# FPGA3.net
KiCad netlist of a schematic drawn in Altium Designer
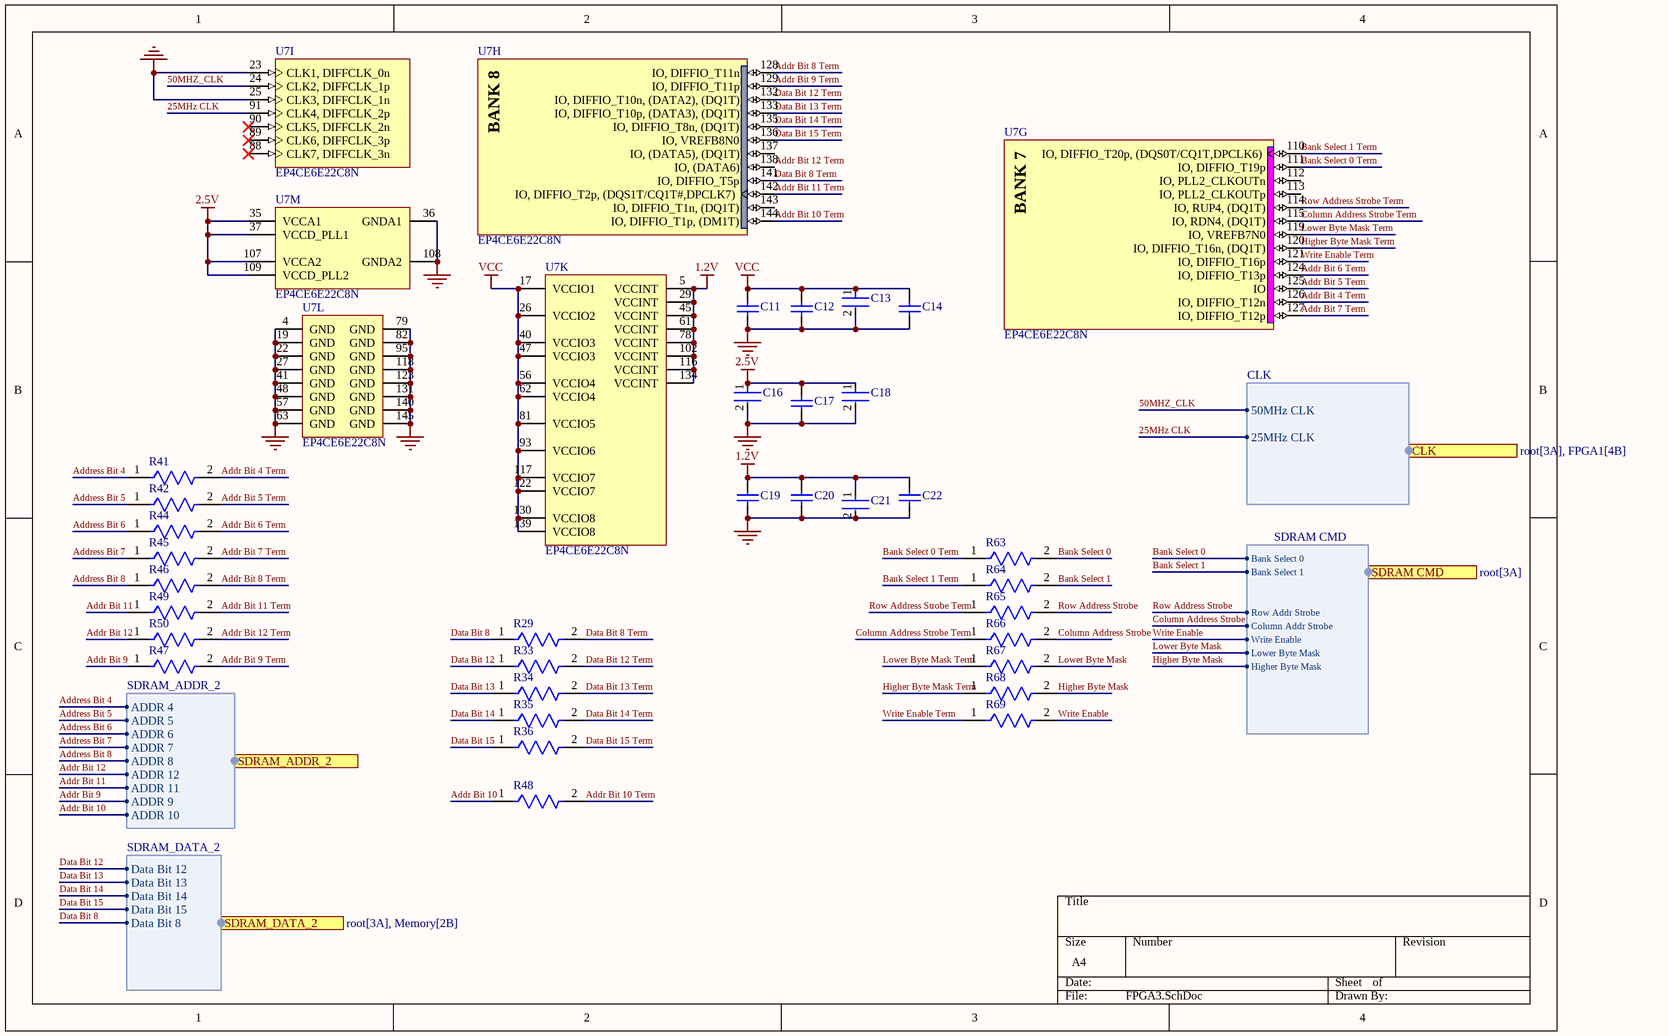
[diagram p0: FPGA3.SchDoc]

(export (version "E")
  (design (tool "Eeschema 10.0.6"))
  (components
    (comp (ref "C11")
      (value "C0603C105K9PACTU")
      (footprint "CAPC1608X90X35LL15T15")
      (fields (field (name "MANUFACTURER") "Kemet"))
      (libsource (lib "Altium Content Vault") (part "CAP"))
    )
    (comp (ref "C12")
      (value "C0603C105K9PACTU")
      (footprint "CAPC1608X90X35LL15T15")
      (fields (field (name "MANUFACTURER") "Kemet"))
      (libsource (lib "Altium Content Vault") (part "CAP"))
    )
    (comp (ref "C13")
      (value "CC0603KRX7R9BB104")
      (footprint "FP-CC0603-DA-MFG")
      (description "CAP CER 0.1UF 50V X7R 0603")
      (fields (field (name "MANUFACTURER") "YAGEO") (field (name "VOLTAGE") "50 V"))
      (libsource (lib "Altium Content Vault") (part "11868f565c42a9108669ba33697ecf6"))
    )
    (comp (ref "C14")
      (value "C0805S472K5RACTU")
      (footprint "CAPC2013X145X50ML20T25")
      (fields (field (name "MANUFACTURER") "Kemet"))
      (libsource (lib "Altium Content Vault") (part "CAP"))
    )
    (comp (ref "C16")
      (value "CL10B102KB8NNNC")
      (footprint "FP-CL10-IPC_C")
      (description "Cap Ceramic 1nF 50V X7R ±10% Pad SMD 0603 +125°C T/R")
      (fields (field (name "VOLTAGE") "50V") (field (name "TOLERANCE") "10%"))
      (libsource (lib "Altium Content Vault") (part "b4654b650e69147ec39a6b967a45e02"))
    )
    (comp (ref "C17")
      (value "C0805S472K5RACTU")
      (footprint "CAPC2013X145X50ML20T25")
      (fields (field (name "MANUFACTURER") "Kemet"))
      (libsource (lib "Altium Content Vault") (part "CAP"))
    )
    (comp (ref "C18")
      (value "CC0603KRX7R9BB104")
      (footprint "FP-CC0603-DA-MFG")
      (description "CAP CER 0.1UF 50V X7R 0603")
      (fields (field (name "MANUFACTURER") "YAGEO") (field (name "VOLTAGE") "50 V"))
      (libsource (lib "Altium Content Vault") (part "11868f565c42a9108669ba33697ecf6"))
    )
    (comp (ref "C19")
      (value "C0603C105K9PACTU")
      (footprint "CAPC1608X90X35LL15T15")
      (fields (field (name "MANUFACTURER") "Kemet"))
      (libsource (lib "Altium Content Vault") (part "CAP"))
    )
    (comp (ref "C20")
      (value "C0603C105K9PACTU")
      (footprint "CAPC1608X90X35LL15T15")
      (fields (field (name "MANUFACTURER") "Kemet"))
      (libsource (lib "Altium Content Vault") (part "CAP"))
    )
    (comp (ref "C21")
      (value "CC0603KRX7R9BB104")
      (footprint "FP-CC0603-DA-MFG")
      (description "CAP CER 0.1UF 50V X7R 0603")
      (fields (field (name "MANUFACTURER") "YAGEO") (field (name "VOLTAGE") "50 V"))
      (libsource (lib "Altium Content Vault") (part "11868f565c42a9108669ba33697ecf6"))
    )
    (comp (ref "C22")
      (value "C0805S472K5RACTU")
      (footprint "CAPC2013X145X50ML20T25")
      (fields (field (name "MANUFACTURER") "Kemet"))
      (libsource (lib "Altium Content Vault") (part "CAP"))
    )
    (comp (ref "R29")
      (value "RT0402BRE0750RL")
      (footprint "FP-RT0402-0_35-MFG")
      (fields (field (name "TOLERANCE") "0.1%"))
      (libsource (lib "Altium Content Vault") (part "1029c3af85768c4190bb7ad29bc67b5"))
    )
    (comp (ref "R33")
      (value "RT0402BRE0750RL")
      (footprint "FP-RT0402-0_35-MFG")
      (fields (field (name "TOLERANCE") "0.1%"))
      (libsource (lib "Altium Content Vault") (part "1029c3af85768c4190bb7ad29bc67b5"))
    )
    (comp (ref "R34")
      (value "RT0402BRE0750RL")
      (footprint "FP-RT0402-0_35-MFG")
      (fields (field (name "TOLERANCE") "0.1%"))
      (libsource (lib "Altium Content Vault") (part "1029c3af85768c4190bb7ad29bc67b5"))
    )
    (comp (ref "R35")
      (value "RT0402BRE0750RL")
      (footprint "FP-RT0402-0_35-MFG")
      (fields (field (name "TOLERANCE") "0.1%"))
      (libsource (lib "Altium Content Vault") (part "1029c3af85768c4190bb7ad29bc67b5"))
    )
    (comp (ref "R36")
      (value "RT0402BRE0750RL")
      (footprint "FP-RT0402-0_35-MFG")
      (fields (field (name "TOLERANCE") "0.1%"))
      (libsource (lib "Altium Content Vault") (part "1029c3af85768c4190bb7ad29bc67b5"))
    )
    (comp (ref "R41")
      (value "RT0402BRE0750RL")
      (footprint "FP-RT0402-0_35-MFG")
      (fields (field (name "TOLERANCE") "0.1%"))
      (libsource (lib "Altium Content Vault") (part "1029c3af85768c4190bb7ad29bc67b5"))
    )
    (comp (ref "R42")
      (value "RT0402BRE0750RL")
      (footprint "FP-RT0402-0_35-MFG")
      (fields (field (name "TOLERANCE") "0.1%"))
      (libsource (lib "Altium Content Vault") (part "1029c3af85768c4190bb7ad29bc67b5"))
    )
    (comp (ref "R44")
      (value "RT0402BRE0750RL")
      (footprint "FP-RT0402-0_35-MFG")
      (fields (field (name "TOLERANCE") "0.1%"))
      (libsource (lib "Altium Content Vault") (part "1029c3af85768c4190bb7ad29bc67b5"))
    )
    (comp (ref "R45")
      (value "RT0402BRE0750RL")
      (footprint "FP-RT0402-0_35-MFG")
      (fields (field (name "TOLERANCE") "0.1%"))
      (libsource (lib "Altium Content Vault") (part "1029c3af85768c4190bb7ad29bc67b5"))
    )
    (comp (ref "R46")
      (value "RT0402BRE0750RL")
      (footprint "FP-RT0402-0_35-MFG")
      (fields (field (name "TOLERANCE") "0.1%"))
      (libsource (lib "Altium Content Vault") (part "1029c3af85768c4190bb7ad29bc67b5"))
    )
    (comp (ref "R47")
      (value "RT0402BRE0750RL")
      (footprint "FP-RT0402-0_35-MFG")
      (fields (field (name "TOLERANCE") "0.1%"))
      (libsource (lib "Altium Content Vault") (part "1029c3af85768c4190bb7ad29bc67b5"))
    )
    (comp (ref "R48")
      (value "RT0402BRE0750RL")
      (footprint "FP-RT0402-0_35-MFG")
      (fields (field (name "TOLERANCE") "0.1%"))
      (libsource (lib "Altium Content Vault") (part "1029c3af85768c4190bb7ad29bc67b5"))
    )
    (comp (ref "R49")
      (value "RT0402BRE0750RL")
      (footprint "FP-RT0402-0_35-MFG")
      (fields (field (name "TOLERANCE") "0.1%"))
      (libsource (lib "Altium Content Vault") (part "1029c3af85768c4190bb7ad29bc67b5"))
    )
    (comp (ref "R50")
      (value "RT0402BRE0750RL")
      (footprint "FP-RT0402-0_35-MFG")
      (fields (field (name "TOLERANCE") "0.1%"))
      (libsource (lib "Altium Content Vault") (part "1029c3af85768c4190bb7ad29bc67b5"))
    )
    (comp (ref "R63")
      (value "RT0402BRE0750RL")
      (footprint "FP-RT0402-0_35-MFG")
      (fields (field (name "TOLERANCE") "0.1%"))
      (libsource (lib "Altium Content Vault") (part "1029c3af85768c4190bb7ad29bc67b5"))
    )
    (comp (ref "R64")
      (value "RT0402BRE0750RL")
      (footprint "FP-RT0402-0_35-MFG")
      (fields (field (name "TOLERANCE") "0.1%"))
      (libsource (lib "Altium Content Vault") (part "1029c3af85768c4190bb7ad29bc67b5"))
    )
    (comp (ref "R65")
      (value "RT0402BRE0750RL")
      (footprint "FP-RT0402-0_35-MFG")
      (fields (field (name "TOLERANCE") "0.1%"))
      (libsource (lib "Altium Content Vault") (part "1029c3af85768c4190bb7ad29bc67b5"))
    )
    (comp (ref "R66")
      (value "RT0402BRE0750RL")
      (footprint "FP-RT0402-0_35-MFG")
      (fields (field (name "TOLERANCE") "0.1%"))
      (libsource (lib "Altium Content Vault") (part "1029c3af85768c4190bb7ad29bc67b5"))
    )
    (comp (ref "R67")
      (value "RT0402BRE0750RL")
      (footprint "FP-RT0402-0_35-MFG")
      (fields (field (name "TOLERANCE") "0.1%"))
      (libsource (lib "Altium Content Vault") (part "1029c3af85768c4190bb7ad29bc67b5"))
    )
    (comp (ref "R68")
      (value "RT0402BRE0750RL")
      (footprint "FP-RT0402-0_35-MFG")
      (fields (field (name "TOLERANCE") "0.1%"))
      (libsource (lib "Altium Content Vault") (part "1029c3af85768c4190bb7ad29bc67b5"))
    )
    (comp (ref "R69")
      (value "RT0402BRE0750RL")
      (footprint "FP-RT0402-0_35-MFG")
      (fields (field (name "TOLERANCE") "0.1%"))
      (libsource (lib "Altium Content Vault") (part "1029c3af85768c4190bb7ad29bc67b5"))
    )
    (comp (ref "U7")
      (value "EP4CE6E22C8N")
      (footprint "EQFP144_A-165_D2-54_M")
      (fields (field (name "MANUFACTURER") "Altera"))
      (libsource (lib "Altium Content Vault") (part "FPGA-ALEP4C-EP4CE6-E144"))
    )
  )
  (nets
    (net (code "6") (name "/25MHz CLK") (class "Default")
      (node (ref "U7") (pin "91") (pinfunction "CLK4,_DIFFCLK_2p_91") (pintype "input"))
    )
    (net (code "7") (name "/50MHZ_CLK") (class "Default")
      (node (ref "U7") (pin "24") (pinfunction "CLK2,_DIFFCLK_1p_24") (pintype "input"))
    )
    (net (code "8") (name "/Addr Bit 4 Term") (class "Default")
      (node (ref "R41") (pin "2") (pinfunction "2_2") (pintype "passive"))
      (node (ref "U7") (pin "126") (pinfunction "IO,_DIFFIO_T12n_126") (pintype "bidirectional"))
    )
    (net (code "9") (name "/Addr Bit 5 Term") (class "Default")
      (node (ref "R42") (pin "2") (pinfunction "2_2") (pintype "passive"))
      (node (ref "U7") (pin "125") (pinfunction "IO_125") (pintype "bidirectional"))
    )
    (net (code "10") (name "/Addr Bit 6 Term") (class "Default")
      (node (ref "R44") (pin "2") (pinfunction "2_2") (pintype "passive"))
      (node (ref "U7") (pin "124") (pinfunction "IO,_DIFFIO_T13p_124") (pintype "bidirectional"))
    )
    (net (code "11") (name "/Addr Bit 7 Term") (class "Default")
      (node (ref "R45") (pin "2") (pinfunction "2_2") (pintype "passive"))
      (node (ref "U7") (pin "127") (pinfunction "IO,_DIFFIO_T12p_127") (pintype "bidirectional"))
    )
    (net (code "12") (name "/Addr Bit 8 Term") (class "Default")
      (node (ref "R46") (pin "2") (pinfunction "2_2") (pintype "passive"))
      (node (ref "U7") (pin "128") (pinfunction "IO,_DIFFIO_T11n_128") (pintype "bidirectional"))
    )
    (net (code "13") (name "/Addr Bit 9") (class "Default")
      (node (ref "R47") (pin "1") (pinfunction "1_1") (pintype "passive"))
    )
    (net (code "14") (name "/Addr Bit 9 Term") (class "Default")
      (node (ref "R47") (pin "2") (pinfunction "2_2") (pintype "passive"))
      (node (ref "U7") (pin "129") (pinfunction "IO,_DIFFIO_T11p_129") (pintype "bidirectional"))
    )
    (net (code "15") (name "/Addr Bit 10") (class "Default")
      (node (ref "R48") (pin "1") (pinfunction "1_1") (pintype "passive"))
    )
    (net (code "16") (name "/Addr Bit 10 Term") (class "Default")
      (node (ref "R48") (pin "2") (pinfunction "2_2") (pintype "passive"))
      (node (ref "U7") (pin "144") (pinfunction "IO,_DIFFIO_T1p,_(DM1T)_144") (pintype "bidirectional"))
    )
    (net (code "17") (name "/Addr Bit 11") (class "Default")
      (node (ref "R49") (pin "1") (pinfunction "1_1") (pintype "passive"))
    )
    (net (code "18") (name "/Addr Bit 11 Term") (class "Default")
      (node (ref "R49") (pin "2") (pinfunction "2_2") (pintype "passive"))
      (node (ref "U7") (pin "142") (pinfunction "IO,_DIFFIO_T2p,_(DQS1T/CQ1T#,DPCLK7)_142") (pintype "bidirectional"))
    )
    (net (code "19") (name "/Addr Bit 12") (class "Default")
      (node (ref "R50") (pin "1") (pinfunction "1_1") (pintype "passive"))
    )
    (net (code "20") (name "/Addr Bit 12 Term") (class "Default")
      (node (ref "R50") (pin "2") (pinfunction "2_2") (pintype "passive"))
      (node (ref "U7") (pin "138") (pinfunction "IO,_(DATA6)_138") (pintype "bidirectional"))
    )
    (net (code "21") (name "/Address Bit 4") (class "Default")
      (node (ref "R41") (pin "1") (pinfunction "1_1") (pintype "passive"))
    )
    (net (code "22") (name "/Address Bit 5") (class "Default")
      (node (ref "R42") (pin "1") (pinfunction "1_1") (pintype "passive"))
    )
    (net (code "23") (name "/Address Bit 6") (class "Default")
      (node (ref "R44") (pin "1") (pinfunction "1_1") (pintype "passive"))
    )
    (net (code "24") (name "/Address Bit 7") (class "Default")
      (node (ref "R45") (pin "1") (pinfunction "1_1") (pintype "passive"))
    )
    (net (code "25") (name "/Address Bit 8") (class "Default")
      (node (ref "R46") (pin "1") (pinfunction "1_1") (pintype "passive"))
    )
    (net (code "26") (name "/Bank Select 0") (class "Default")
      (node (ref "R63") (pin "2") (pinfunction "2_2") (pintype "passive"))
    )
    (net (code "27") (name "/Bank Select 0 Term") (class "Default")
      (node (ref "R63") (pin "1") (pinfunction "1_1") (pintype "passive"))
      (node (ref "U7") (pin "111") (pinfunction "IO,_DIFFIO_T19p_111") (pintype "bidirectional"))
    )
    (net (code "28") (name "/Bank Select 1") (class "Default")
      (node (ref "R64") (pin "2") (pinfunction "2_2") (pintype "passive"))
    )
    (net (code "29") (name "/Bank Select 1 Term") (class "Default")
      (node (ref "R64") (pin "1") (pinfunction "1_1") (pintype "passive"))
      (node (ref "U7") (pin "110") (pinfunction "IO,_DIFFIO_T20p,_(DQS0T/CQ1T,DPCLK6)_110") (pintype "bidirectional"))
    )
    (net (code "30") (name "/Column Address Strobe") (class "Default")
      (node (ref "R66") (pin "2") (pinfunction "2_2") (pintype "passive"))
    )
    (net (code "31") (name "/Column Address Strobe Term") (class "Default")
      (node (ref "R66") (pin "1") (pinfunction "1_1") (pintype "passive"))
      (node (ref "U7") (pin "115") (pinfunction "IO,_RDN4,_(DQ1T)_115") (pintype "bidirectional"))
    )
    (net (code "32") (name "/Data Bit 8") (class "Default")
      (node (ref "R29") (pin "1") (pinfunction "1_1") (pintype "passive"))
    )
    (net (code "33") (name "/Data Bit 8 Term") (class "Default")
      (node (ref "R29") (pin "2") (pinfunction "2_2") (pintype "passive"))
      (node (ref "U7") (pin "141") (pinfunction "IO,_DIFFIO_T5p_141") (pintype "bidirectional"))
    )
    (net (code "34") (name "/Data Bit 12") (class "Default")
      (node (ref "R33") (pin "1") (pinfunction "1_1") (pintype "passive"))
    )
    (net (code "35") (name "/Data Bit 12 Term") (class "Default")
      (node (ref "R33") (pin "2") (pinfunction "2_2") (pintype "passive"))
      (node (ref "U7") (pin "132") (pinfunction "IO,_DIFFIO_T10n,_(DATA2),_(DQ1T)_132") (pintype "bidirectional"))
    )
    (net (code "36") (name "/Data Bit 13") (class "Default")
      (node (ref "R34") (pin "1") (pinfunction "1_1") (pintype "passive"))
    )
    (net (code "37") (name "/Data Bit 13 Term") (class "Default")
      (node (ref "R34") (pin "2") (pinfunction "2_2") (pintype "passive"))
      (node (ref "U7") (pin "133") (pinfunction "IO,_DIFFIO_T10p,_(DATA3),_(DQ1T)_133") (pintype "bidirectional"))
    )
    (net (code "38") (name "/Data Bit 14") (class "Default")
      (node (ref "R35") (pin "1") (pinfunction "1_1") (pintype "passive"))
    )
    (net (code "39") (name "/Data Bit 14 Term") (class "Default")
      (node (ref "R35") (pin "2") (pinfunction "2_2") (pintype "passive"))
      (node (ref "U7") (pin "135") (pinfunction "IO,_DIFFIO_T8n,_(DQ1T)_135") (pintype "bidirectional"))
    )
    (net (code "40") (name "/Data Bit 15") (class "Default")
      (node (ref "R36") (pin "1") (pinfunction "1_1") (pintype "passive"))
    )
    (net (code "41") (name "/Data Bit 15 Term") (class "Default")
      (node (ref "R36") (pin "2") (pinfunction "2_2") (pintype "passive"))
      (node (ref "U7") (pin "136") (pinfunction "IO,_VREFB8N0_136") (pintype "bidirectional"))
    )
    (net (code "42") (name "/Higher Byte Mask") (class "Default")
      (node (ref "R68") (pin "2") (pinfunction "2_2") (pintype "passive"))
    )
    (net (code "43") (name "/Higher Byte Mask Term") (class "Default")
      (node (ref "R68") (pin "1") (pinfunction "1_1") (pintype "passive"))
      (node (ref "U7") (pin "120") (pinfunction "IO,_DIFFIO_T16n,_(DQ1T)_120") (pintype "bidirectional"))
    )
    (net (code "44") (name "/Lower Byte Mask") (class "Default")
      (node (ref "R67") (pin "2") (pinfunction "2_2") (pintype "passive"))
    )
    (net (code "45") (name "/Lower Byte Mask Term") (class "Default")
      (node (ref "R67") (pin "1") (pinfunction "1_1") (pintype "passive"))
      (node (ref "U7") (pin "119") (pinfunction "IO,_VREFB7N0_119") (pintype "bidirectional"))
    )
    (net (code "46") (name "/Row Address Strobe") (class "Default")
      (node (ref "R65") (pin "2") (pinfunction "2_2") (pintype "passive"))
    )
    (net (code "47") (name "/Row Address Strobe Term") (class "Default")
      (node (ref "R65") (pin "1") (pinfunction "1_1") (pintype "passive"))
      (node (ref "U7") (pin "114") (pinfunction "IO,_RUP4,_(DQ1T)_114") (pintype "bidirectional"))
    )
    (net (code "48") (name "/Write Enable") (class "Default")
      (node (ref "R69") (pin "2") (pinfunction "2_2") (pintype "passive"))
    )
    (net (code "49") (name "/Write Enable Term") (class "Default")
      (node (ref "R69") (pin "1") (pinfunction "1_1") (pintype "passive"))
      (node (ref "U7") (pin "121") (pinfunction "IO,_DIFFIO_T16p_121") (pintype "bidirectional"))
    )
    (net (code "54") (name "1.2V") (class "Default")
      (node (ref "C19") (pin "2") (pinfunction "2_2") (pintype "passive"))
      (node (ref "C20") (pin "2") (pinfunction "2_2") (pintype "passive"))
      (node (ref "C21") (pin "1") (pinfunction "1_1") (pintype "passive"))
      (node (ref "C22") (pin "2") (pinfunction "2_2") (pintype "passive"))
      (node (ref "U7") (pin "102") (pinfunction "VCCINT_102") (pintype "power_in"))
      (node (ref "U7") (pin "116") (pinfunction "VCCINT_116") (pintype "power_in"))
      (node (ref "U7") (pin "134") (pinfunction "VCCINT_134") (pintype "power_in"))
      (node (ref "U7") (pin "29") (pinfunction "VCCINT_29") (pintype "power_in"))
      (node (ref "U7") (pin "45") (pinfunction "VCCINT_45") (pintype "power_in"))
      (node (ref "U7") (pin "5") (pinfunction "VCCINT_5") (pintype "power_in"))
      (node (ref "U7") (pin "61") (pinfunction "VCCINT_61") (pintype "power_in"))
      (node (ref "U7") (pin "78") (pinfunction "VCCINT_78") (pintype "power_in"))
    )
    (net (code "55") (name "2.5V") (class "Default")
      (node (ref "C16") (pin "1") (pinfunction "1_1") (pintype "passive"))
      (node (ref "C17") (pin "2") (pinfunction "2_2") (pintype "passive"))
      (node (ref "C18") (pin "1") (pinfunction "1_1") (pintype "passive"))
      (node (ref "U7") (pin "107") (pinfunction "VCCA2_107") (pintype "power_in"))
      (node (ref "U7") (pin "109") (pinfunction "VCCD_PLL2_109") (pintype "power_in"))
      (node (ref "U7") (pin "35") (pinfunction "VCCA1_35") (pintype "power_in"))
      (node (ref "U7") (pin "37") (pinfunction "VCCD_PLL1_37") (pintype "power_in"))
    )
    (net (code "56") (name "GND") (class "Default")
      (node (ref "C11") (pin "1") (pinfunction "1_1") (pintype "passive"))
      (node (ref "C12") (pin "1") (pinfunction "1_1") (pintype "passive"))
      (node (ref "C13") (pin "2") (pinfunction "2_2") (pintype "passive"))
      (node (ref "C14") (pin "1") (pinfunction "1_1") (pintype "passive"))
      (node (ref "C16") (pin "2") (pinfunction "2_2") (pintype "passive"))
      (node (ref "C17") (pin "1") (pinfunction "1_1") (pintype "passive"))
      (node (ref "C18") (pin "2") (pinfunction "2_2") (pintype "passive"))
      (node (ref "C19") (pin "1") (pinfunction "1_1") (pintype "passive"))
      (node (ref "C20") (pin "1") (pinfunction "1_1") (pintype "passive"))
      (node (ref "C21") (pin "2") (pinfunction "2_2") (pintype "passive"))
      (node (ref "C22") (pin "1") (pinfunction "1_1") (pintype "passive"))
      (node (ref "U7") (pin "108") (pinfunction "GNDA2_108") (pintype "power_in"))
      (node (ref "U7") (pin "118") (pinfunction "GND_118") (pintype "power_in"))
      (node (ref "U7") (pin "123") (pinfunction "GND_123") (pintype "power_in"))
      (node (ref "U7") (pin "131") (pinfunction "GND_131") (pintype "power_in"))
      (node (ref "U7") (pin "140") (pinfunction "GND_140") (pintype "power_in"))
      (node (ref "U7") (pin "145") (pinfunction "GND_145") (pintype "power_in"))
      (node (ref "U7") (pin "19") (pinfunction "GND_19") (pintype "power_in"))
      (node (ref "U7") (pin "22") (pinfunction "GND_22") (pintype "power_in"))
      (node (ref "U7") (pin "23") (pinfunction "CLK1,_DIFFCLK_0n_23") (pintype "input"))
      (node (ref "U7") (pin "25") (pinfunction "CLK3,_DIFFCLK_1n_25") (pintype "input"))
      (node (ref "U7") (pin "27") (pinfunction "GND_27") (pintype "power_in"))
      (node (ref "U7") (pin "36") (pinfunction "GNDA1_36") (pintype "power_in"))
      (node (ref "U7") (pin "4") (pinfunction "GND_4") (pintype "power_in"))
      (node (ref "U7") (pin "41") (pinfunction "GND_41") (pintype "power_in"))
      (node (ref "U7") (pin "48") (pinfunction "GND_48") (pintype "power_in"))
      (node (ref "U7") (pin "57") (pinfunction "GND_57") (pintype "power_in"))
      (node (ref "U7") (pin "63") (pinfunction "GND_63") (pintype "power_in"))
      (node (ref "U7") (pin "79") (pinfunction "GND_79") (pintype "power_in"))
      (node (ref "U7") (pin "82") (pinfunction "GND_82") (pintype "power_in"))
      (node (ref "U7") (pin "95") (pinfunction "GND_95") (pintype "power_in"))
    )
    (net (code "57") (name "VCC") (class "Default")
      (node (ref "C11") (pin "2") (pinfunction "2_2") (pintype "passive"))
      (node (ref "C12") (pin "2") (pinfunction "2_2") (pintype "passive"))
      (node (ref "C13") (pin "1") (pinfunction "1_1") (pintype "passive"))
      (node (ref "C14") (pin "2") (pinfunction "2_2") (pintype "passive"))
      (node (ref "U7") (pin "117") (pinfunction "VCCIO7_117") (pintype "power_in"))
      (node (ref "U7") (pin "122") (pinfunction "VCCIO7_122") (pintype "power_in"))
      (node (ref "U7") (pin "130") (pinfunction "VCCIO8_130") (pintype "power_in"))
      (node (ref "U7") (pin "139") (pinfunction "VCCIO8_139") (pintype "power_in"))
      (node (ref "U7") (pin "17") (pinfunction "VCCIO1_17") (pintype "power_in"))
      (node (ref "U7") (pin "26") (pinfunction "VCCIO2_26") (pintype "power_in"))
      (node (ref "U7") (pin "40") (pinfunction "VCCIO3_40") (pintype "power_in"))
      (node (ref "U7") (pin "47") (pinfunction "VCCIO3_47") (pintype "power_in"))
      (node (ref "U7") (pin "56") (pinfunction "VCCIO4_56") (pintype "power_in"))
      (node (ref "U7") (pin "62") (pinfunction "VCCIO4_62") (pintype "power_in"))
      (node (ref "U7") (pin "81") (pinfunction "VCCIO5_81") (pintype "power_in"))
      (node (ref "U7") (pin "93") (pinfunction "VCCIO6_93") (pintype "power_in"))
    )
    (net (code "58") (name "unconnected-(U7G-IO,_PLL2_CLKOUTn-Pad112)") (class "Default")
      (node (ref "U7") (pin "112") (pinfunction "IO,_PLL2_CLKOUTn_112") (pintype "bidirectional"))
    )
    (net (code "59") (name "unconnected-(U7G-IO,_PLL2_CLKOUTp-Pad113)") (class "Default")
      (node (ref "U7") (pin "113") (pinfunction "IO,_PLL2_CLKOUTp_113") (pintype "bidirectional"))
    )
    (net (code "60") (name "unconnected-(U7H-IO,_(DATA5),_(DQ1T)-Pad137)") (class "Default")
      (node (ref "U7") (pin "137") (pinfunction "IO,_(DATA5),_(DQ1T)_137") (pintype "bidirectional"))
    )
    (net (code "61") (name "unconnected-(U7H-IO,_DIFFIO_T1n,_(DQ1T)-Pad143)") (class "Default")
      (node (ref "U7") (pin "143") (pinfunction "IO,_DIFFIO_T1n,_(DQ1T)_143") (pintype "bidirectional"))
    )
    (net (code "62") (name "unconnected-(U7I-CLK5,_DIFFCLK_2n-Pad90)") (class "Default")
      (node (ref "U7") (pin "90") (pinfunction "CLK5,_DIFFCLK_2n_90") (pintype "input+no_connect"))
    )
    (net (code "63") (name "unconnected-(U7I-CLK6,_DIFFCLK_3p-Pad89)") (class "Default")
      (node (ref "U7") (pin "89") (pinfunction "CLK6,_DIFFCLK_3p_89") (pintype "input+no_connect"))
    )
    (net (code "64") (name "unconnected-(U7I-CLK7,_DIFFCLK_3n-Pad88)") (class "Default")
      (node (ref "U7") (pin "88") (pinfunction "CLK7,_DIFFCLK_3n_88") (pintype "input+no_connect"))
    )
  )
)
